# STM32f407layout_nonintegrated.net
KiCad netlist of a schematic drawn in EAGLE
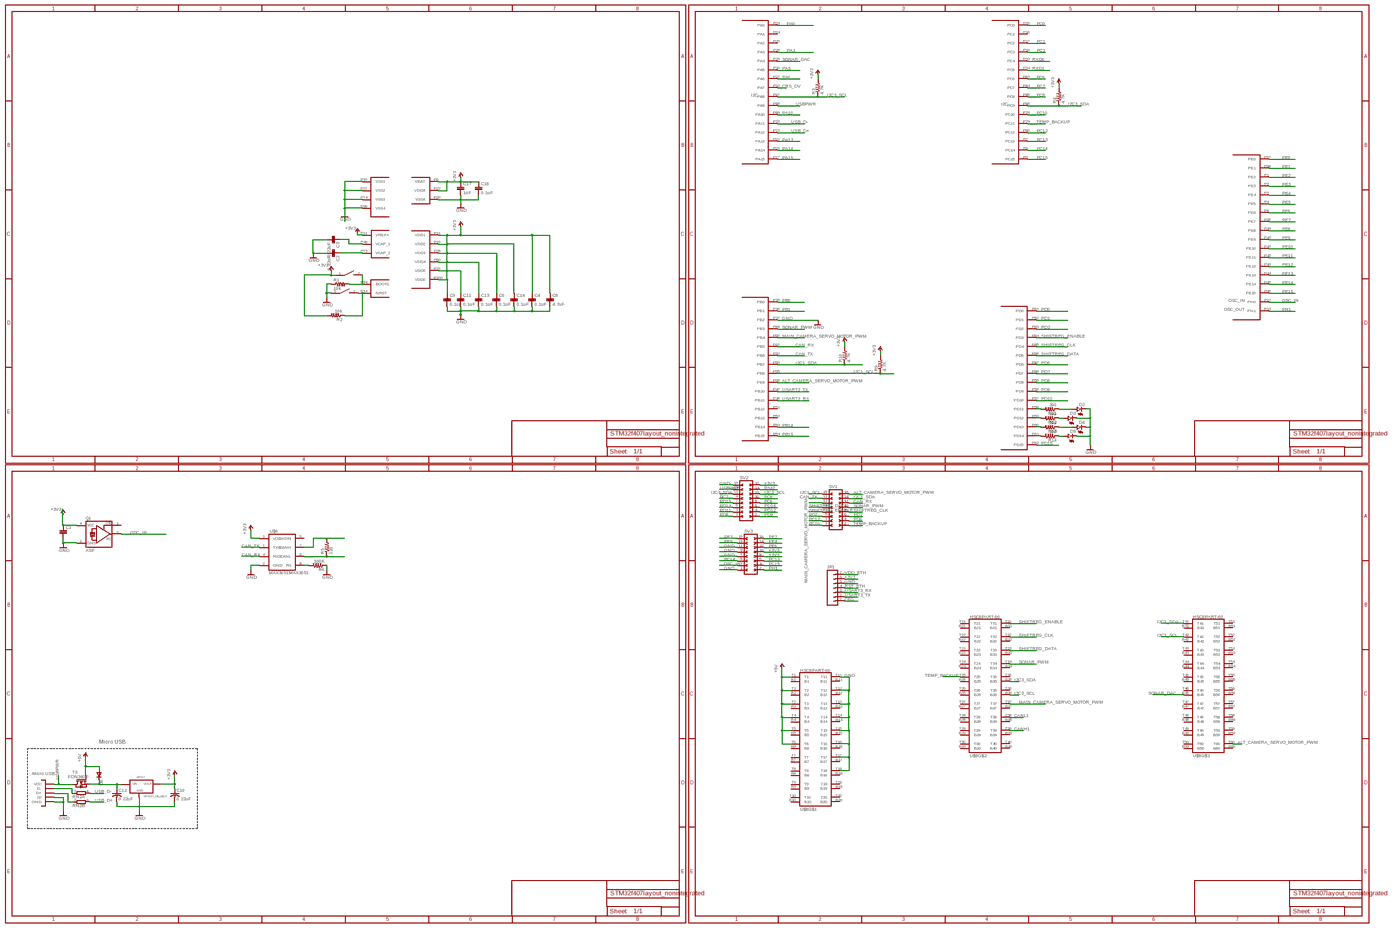
[diagram p0: schematic, sheet 1, overview]
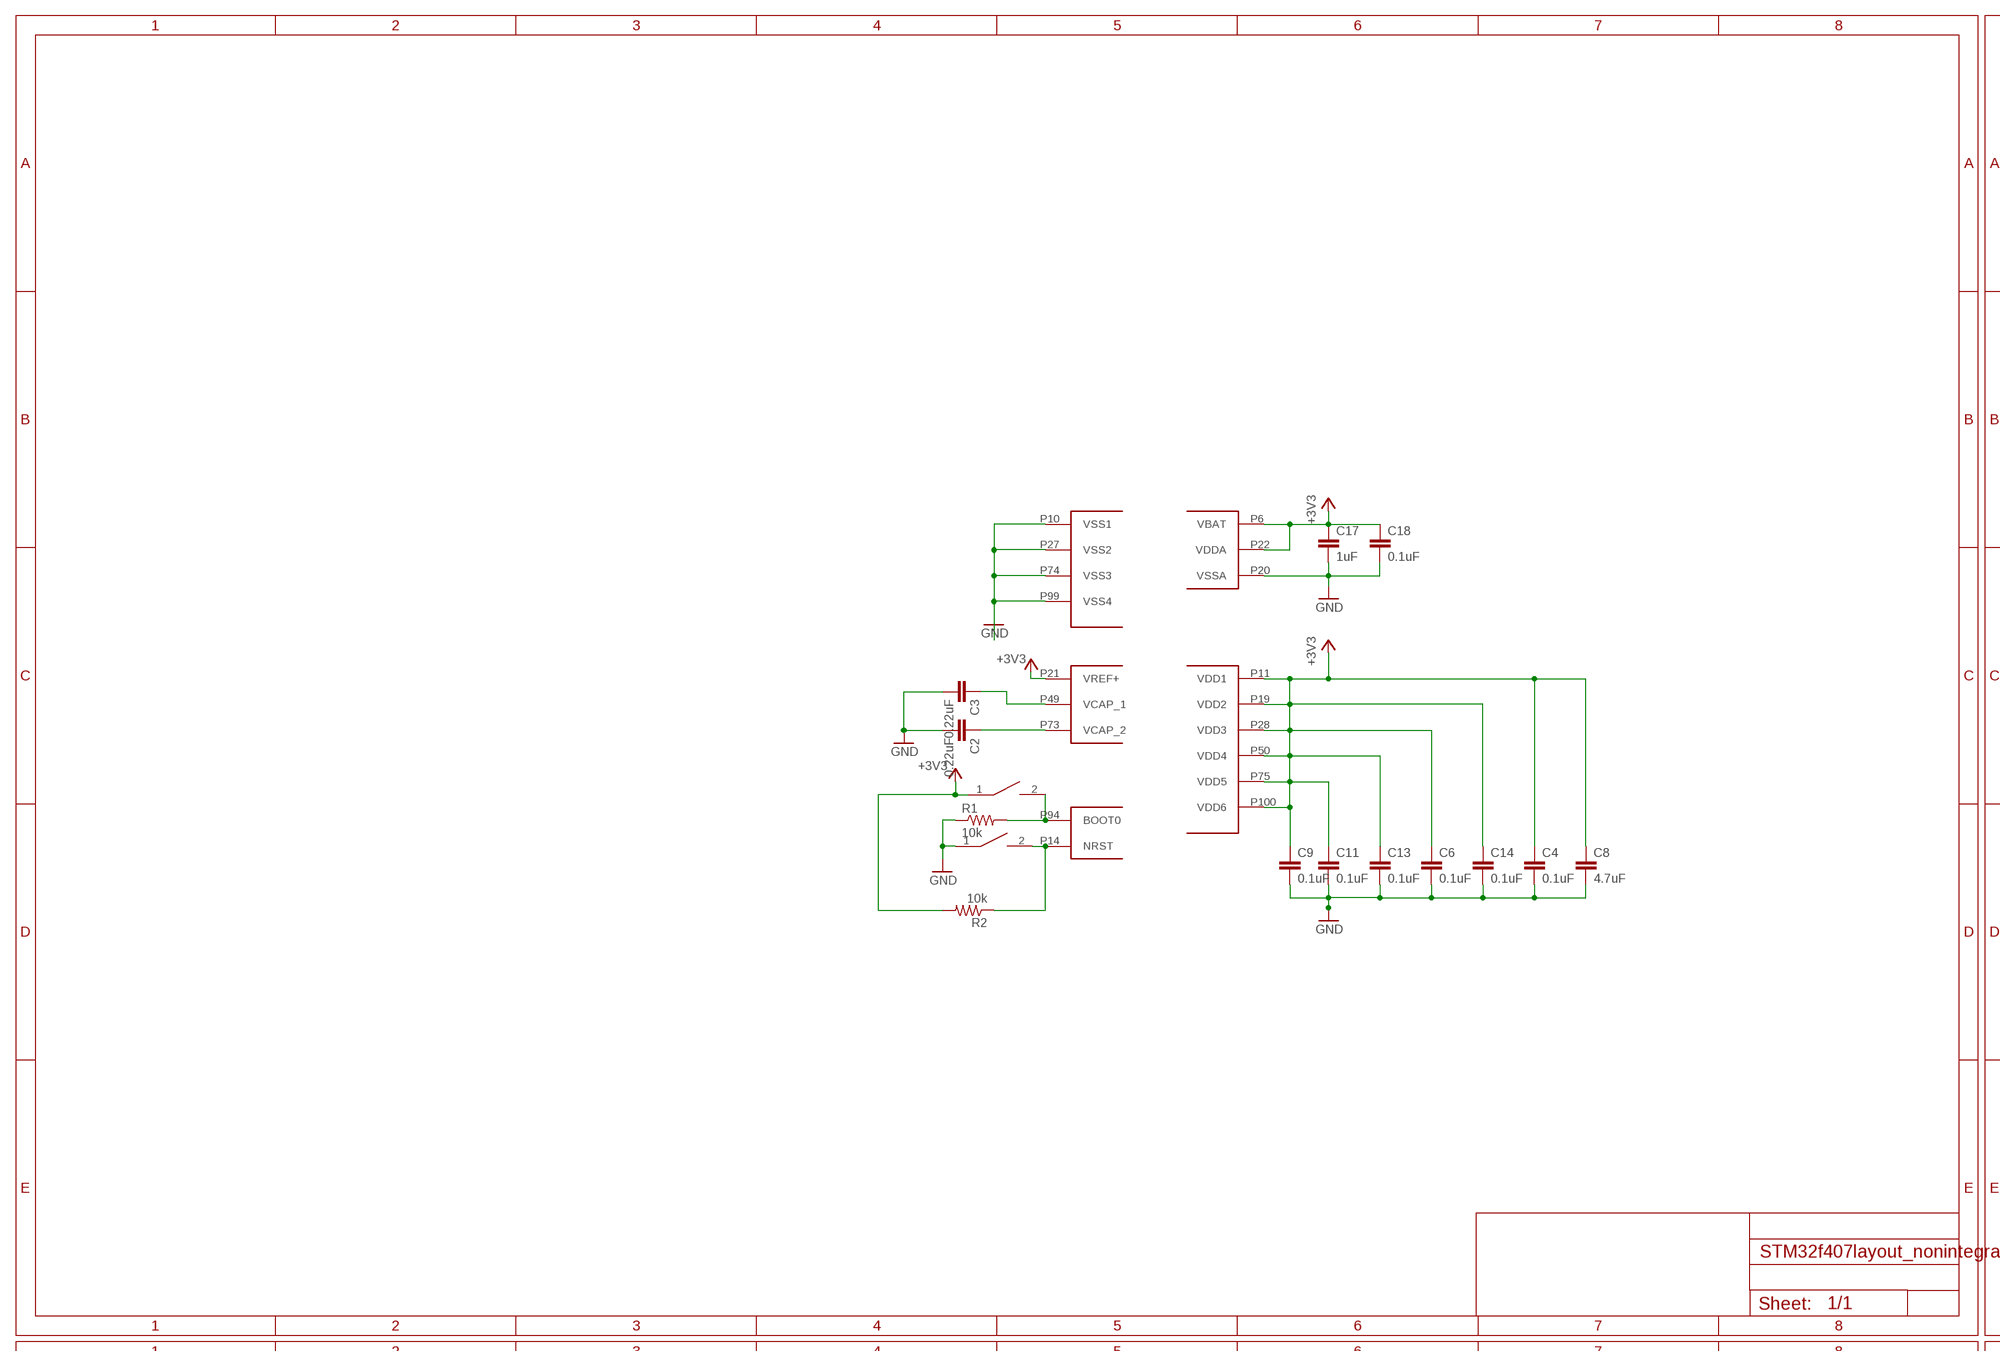
[diagram p1: schematic, sheet 1, part 1 of 4]
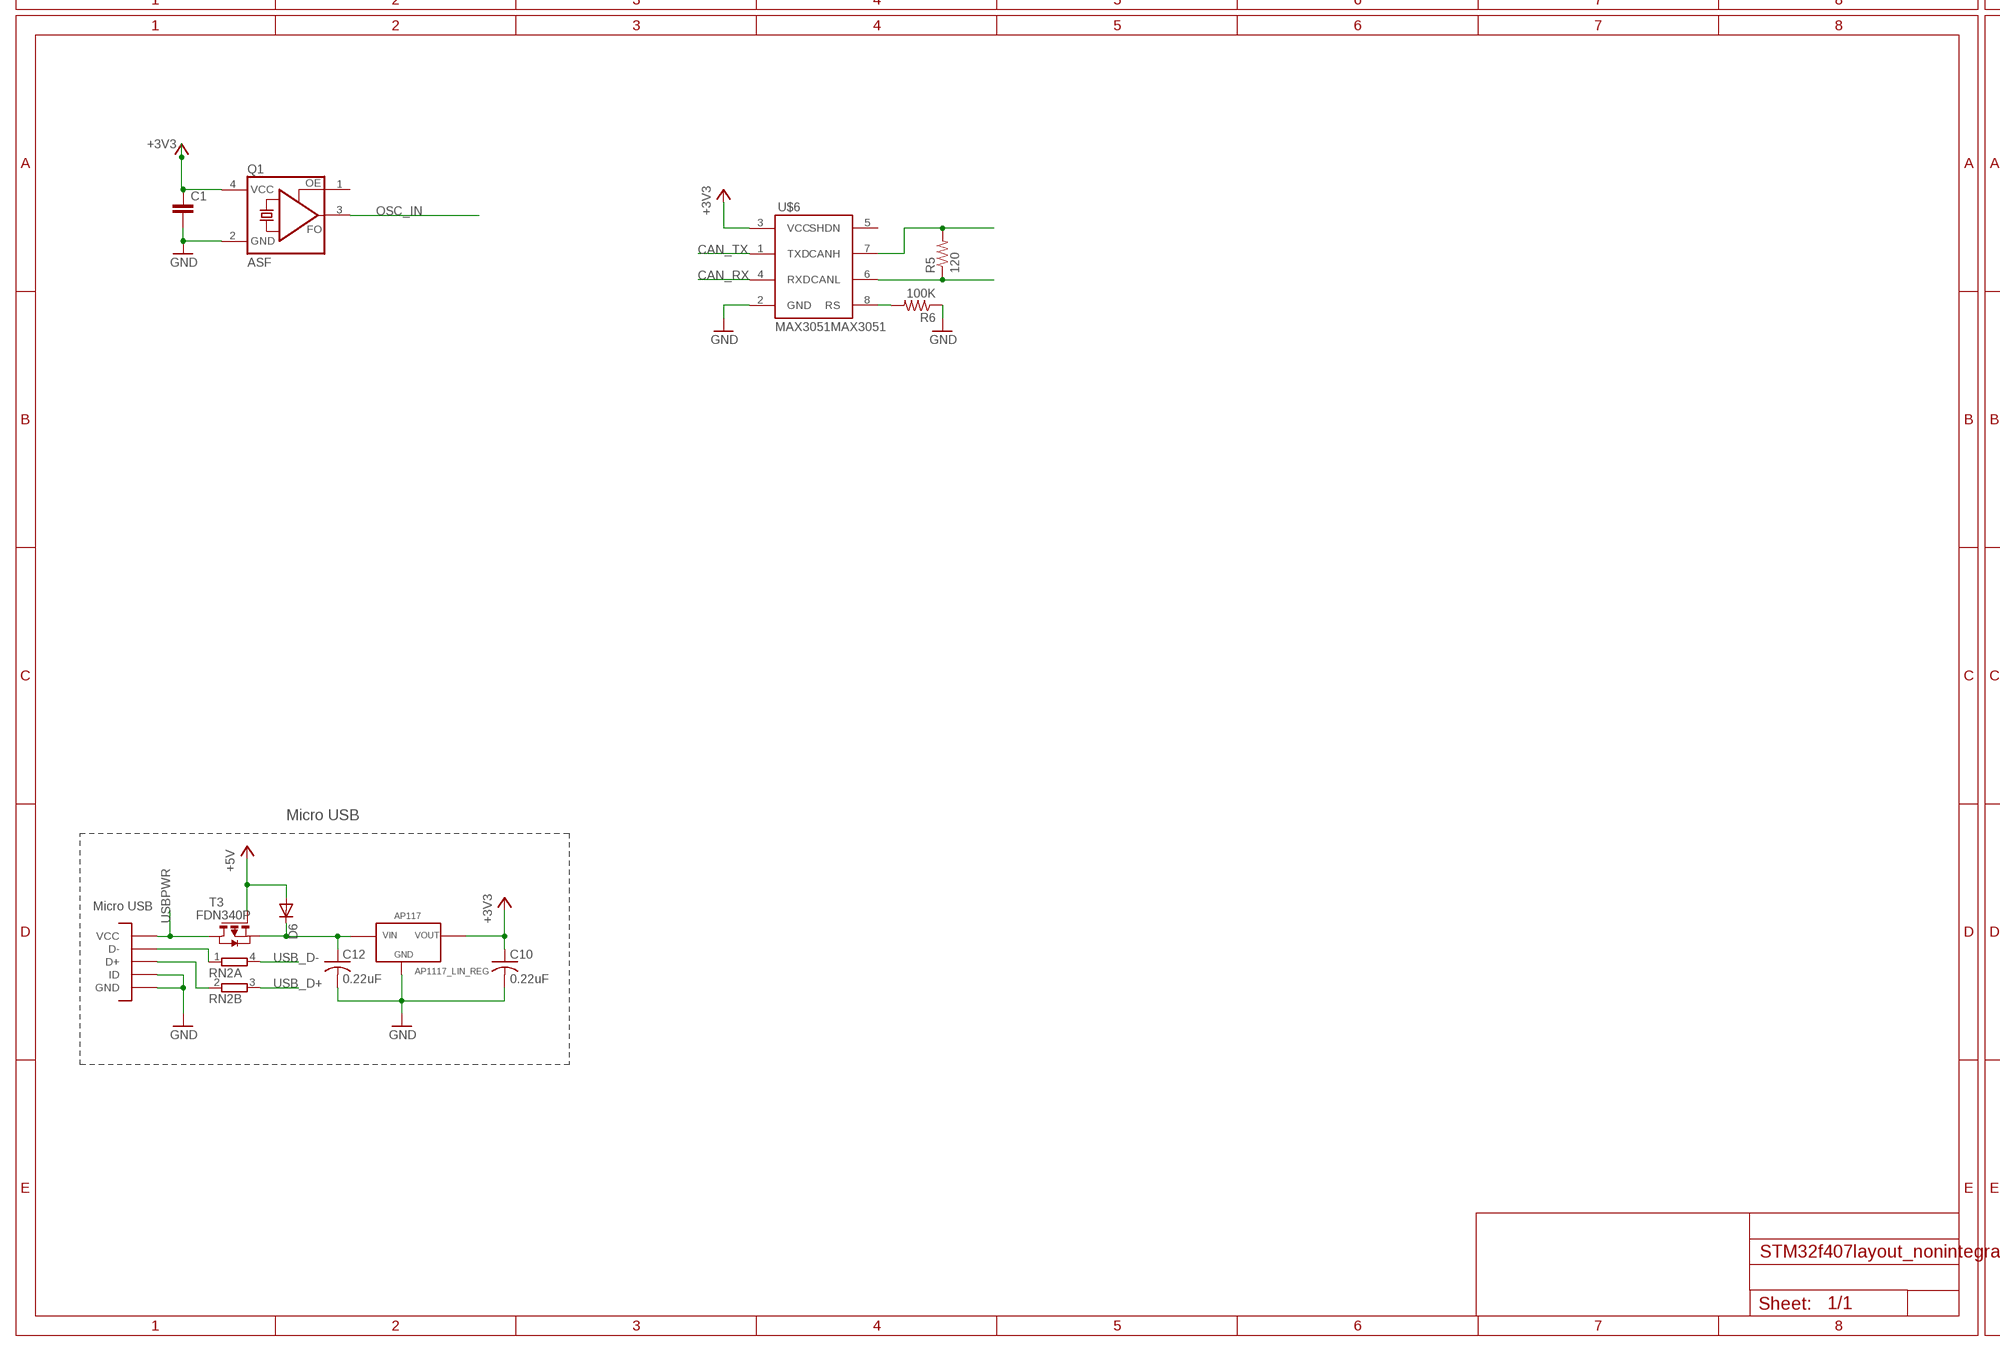
[diagram p2: schematic, sheet 1, part 2 of 4]
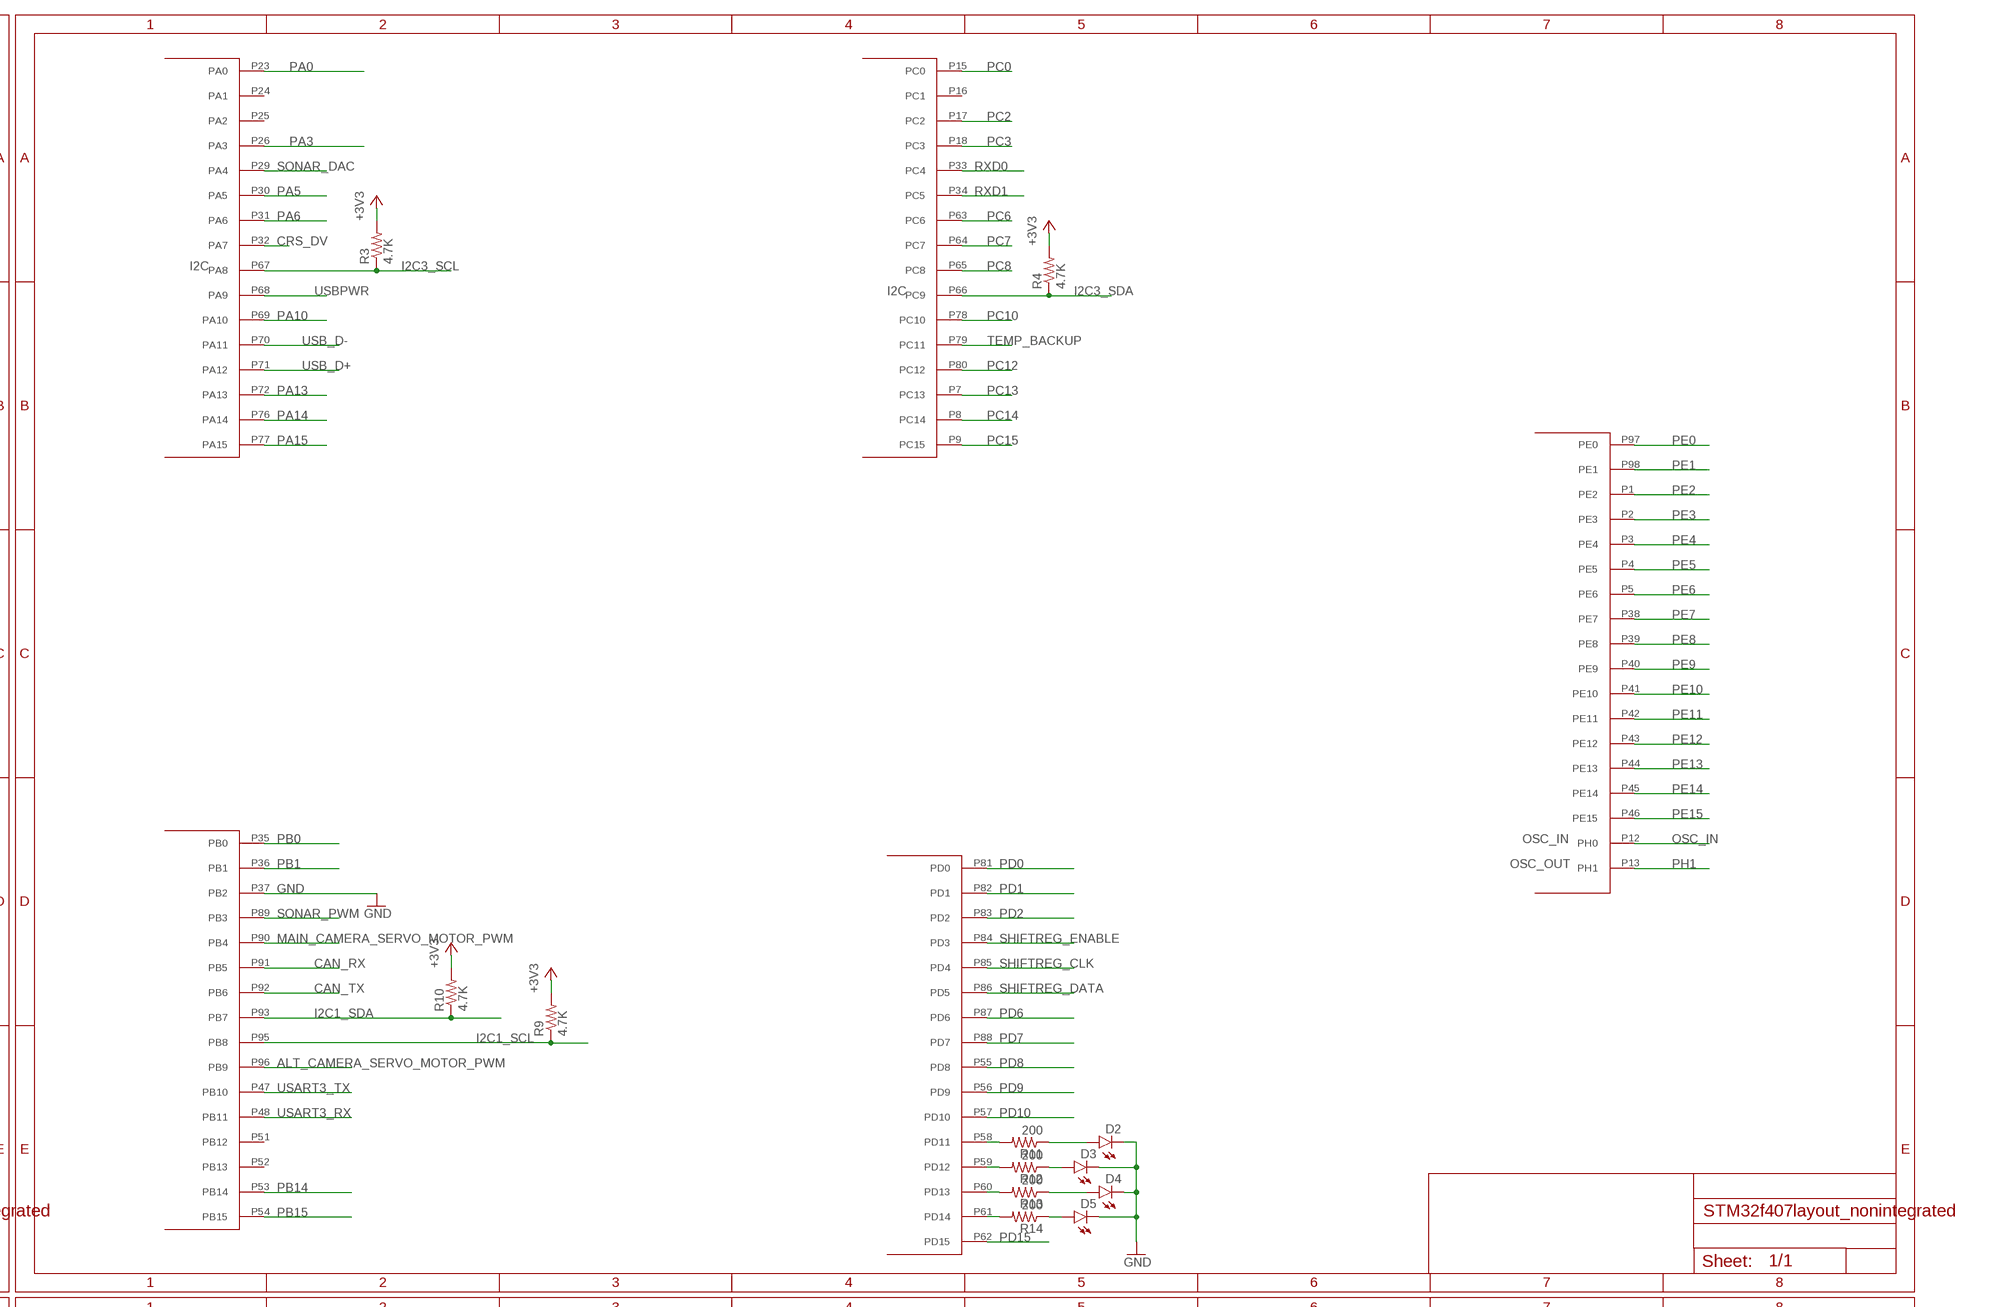
[diagram p3: schematic, sheet 1, part 3 of 4]
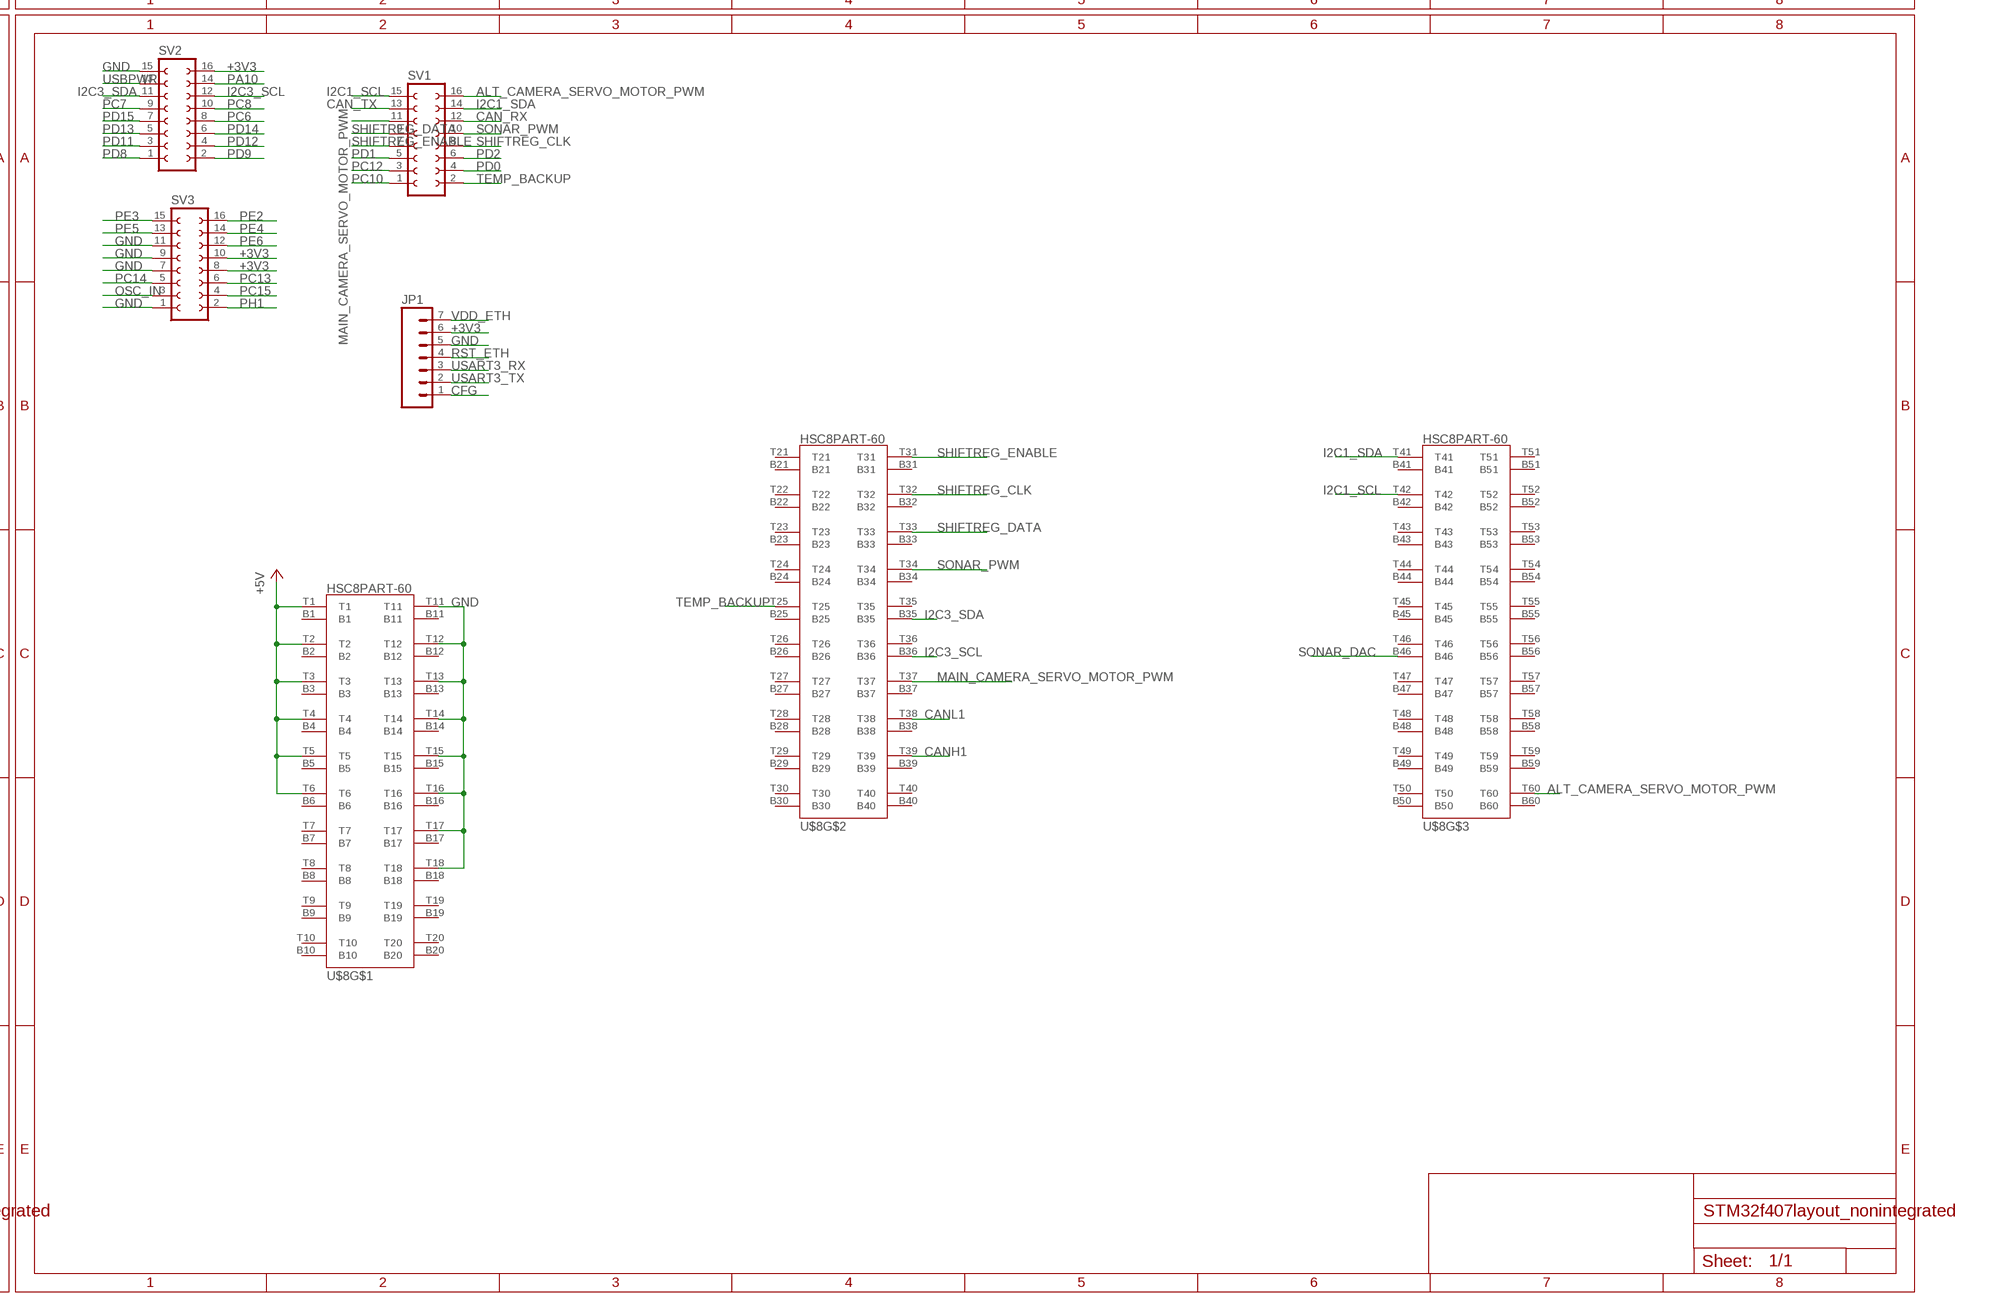
[diagram p4: schematic, sheet 1, part 4 of 4]

(export (version "E")
  (design (tool "Eeschema 10.0.6"))
  (components
    (comp (ref "C1")
      (value "CAP0603-CAP")
      (footprint "eagle-import:0603-CAP")
      (libsource (lib "eagle-import") (part "CAP0603-CAP"))
    )
    (comp (ref "C2")
      (value "0.22uF")
      (footprint "eagle-import:0603-CAP")
      (libsource (lib "eagle-import") (part "CAP0603-CAP"))
    )
    (comp (ref "C3")
      (value "0.22uF")
      (footprint "eagle-import:0603-CAP")
      (libsource (lib "eagle-import") (part "CAP0603-CAP"))
    )
    (comp (ref "C4")
      (value "0.1uF")
      (footprint "eagle-import:0603-CAP")
      (libsource (lib "eagle-import") (part "CAP0603-CAP"))
    )
    (comp (ref "C6")
      (value "0.1uF")
      (footprint "eagle-import:0603-CAP")
      (libsource (lib "eagle-import") (part "CAP0603-CAP"))
    )
    (comp (ref "C8")
      (value "4.7uF")
      (footprint "eagle-import:0603-CAP")
      (libsource (lib "eagle-import") (part "CAP0603-CAP"))
    )
    (comp (ref "C9")
      (value "0.1uF")
      (footprint "eagle-import:0603-CAP")
      (libsource (lib "eagle-import") (part "CAP0603-CAP"))
    )
    (comp (ref "C10")
      (value "0.22uF")
      (footprint "eagle-import:C0603")
      (libsource (lib "eagle-import") (part "C-USC0603"))
    )
    (comp (ref "C11")
      (value "0.1uF")
      (footprint "eagle-import:0603-CAP")
      (libsource (lib "eagle-import") (part "CAP0603-CAP"))
    )
    (comp (ref "C12")
      (value "0.22uF")
      (footprint "eagle-import:C0603")
      (libsource (lib "eagle-import") (part "C-USC0603"))
    )
    (comp (ref "C13")
      (value "0.1uF")
      (footprint "eagle-import:0603-CAP")
      (libsource (lib "eagle-import") (part "CAP0603-CAP"))
    )
    (comp (ref "C14")
      (value "0.1uF")
      (footprint "eagle-import:0603-CAP")
      (libsource (lib "eagle-import") (part "CAP0603-CAP"))
    )
    (comp (ref "C17")
      (value "1uF")
      (footprint "eagle-import:0603-CAP")
      (libsource (lib "eagle-import") (part "CAP0603-CAP"))
    )
    (comp (ref "C18")
      (value "0.1uF")
      (footprint "eagle-import:0603-CAP")
      (libsource (lib "eagle-import") (part "CAP0603-CAP"))
    )
    (comp (ref "D2")
      (value "LED0603")
      (footprint "eagle-import:LED-0603")
      (libsource (lib "eagle-import") (part "LED0603"))
    )
    (comp (ref "D3")
      (value "LED0603")
      (footprint "eagle-import:LED-0603")
      (libsource (lib "eagle-import") (part "LED0603"))
    )
    (comp (ref "D4")
      (value "LED0603")
      (footprint "eagle-import:LED-0603")
      (libsource (lib "eagle-import") (part "LED0603"))
    )
    (comp (ref "D5")
      (value "LED0603")
      (footprint "eagle-import:LED-0603")
      (libsource (lib "eagle-import") (part "LED0603"))
    )
    (comp (ref "D6")
      (value "DIODE-DO-214AC")
      (footprint "eagle-import:DO-214AC")
      (libsource (lib "eagle-import") (part "DIODE-DO-214AC"))
    )
    (comp (ref "JP1")
      (value "M07")
      (footprint "eagle-import:1X07")
      (libsource (lib "eagle-import") (part "M07"))
    )
    (comp (ref "Q1")
      (value "ASF")
      (footprint "eagle-import:ASF")
      (libsource (lib "eagle-import") (part "ASF"))
    )
    (comp (ref "R1")
      (value "10k")
      (footprint "eagle-import:0603-RES")
      (libsource (lib "eagle-import") (part "RESISTOR0603-RES"))
    )
    (comp (ref "R2")
      (value "10k")
      (footprint "eagle-import:0603-RES")
      (libsource (lib "eagle-import") (part "RESISTOR0603-RES"))
    )
    (comp (ref "R3")
      (value "4.7K")
      (footprint "eagle-import:0603-RES")
      (libsource (lib "eagle-import") (part "RESISTOR0603-RES"))
    )
    (comp (ref "R4")
      (value "4.7K")
      (footprint "eagle-import:0603-RES")
      (libsource (lib "eagle-import") (part "RESISTOR0603-RES"))
    )
    (comp (ref "R5")
      (value "120")
      (footprint "eagle-import:0603-RES")
      (libsource (lib "eagle-import") (part "RESISTOR0603-RES"))
    )
    (comp (ref "R6")
      (value "100K")
      (footprint "eagle-import:0603-RES")
      (libsource (lib "eagle-import") (part "RESISTOR0603-RES"))
    )
    (comp (ref "R9")
      (value "4.7K")
      (footprint "eagle-import:0603-RES")
      (libsource (lib "eagle-import") (part "RESISTOR0603-RES"))
    )
    (comp (ref "R10")
      (value "4.7K")
      (footprint "eagle-import:0603-RES")
      (libsource (lib "eagle-import") (part "RESISTOR0603-RES"))
    )
    (comp (ref "R11")
      (value "200")
      (footprint "eagle-import:0603-RES")
      (libsource (lib "eagle-import") (part "RESISTOR0603-RES"))
    )
    (comp (ref "R12")
      (value "200")
      (footprint "eagle-import:0603-RES")
      (libsource (lib "eagle-import") (part "RESISTOR0603-RES"))
    )
    (comp (ref "R13")
      (value "200")
      (footprint "eagle-import:0603-RES")
      (libsource (lib "eagle-import") (part "RESISTOR0603-RES"))
    )
    (comp (ref "R14")
      (value "200")
      (footprint "eagle-import:0603-RES")
      (libsource (lib "eagle-import") (part "RESISTOR0603-RES"))
    )
    (comp (ref "RN2")
      (value "2R-NEXBV4V")
      (footprint "eagle-import:EXBV4V")
      (fields (field (name "MF") "Rohm Semiconductor") (field (name "MPN") "MNR12ERAPJ220"))
      (libsource (lib "eagle-import") (part "2R-NEXBV4V"))
    )
    (comp (ref "SV1")
      (value "FE08-2")
      (footprint "eagle-import:FE08-2")
      (libsource (lib "eagle-import") (part "FE08-2"))
    )
    (comp (ref "SV2")
      (value "FE08-2")
      (footprint "eagle-import:FE08-2")
      (libsource (lib "eagle-import") (part "FE08-2"))
    )
    (comp (ref "SV3")
      (value "FE08-2")
      (footprint "eagle-import:FE08-2")
      (libsource (lib "eagle-import") (part "FE08-2"))
    )
    (comp (ref "T3")
      (value "FDN340P")
      (footprint "eagle-import:SOT-23")
      (libsource (lib "eagle-import") (part "FDN340P"))
    )
    (comp (ref "T4")
      (value "AP1117_LIN_REG")
      (footprint "eagle-import:SOT223")
      (libsource (lib "eagle-import") (part "AP1117_LIN_REG"))
    )
    (comp (ref "U$1")
      (value "STM32F4")
      (footprint "eagle-import:LQFP100")
      (libsource (lib "eagle-import") (part "STM32F4"))
    )
    (comp (ref "U$2")
      (value "SWITCH")
      (footprint "eagle-import:SW_2512")
      (libsource (lib "eagle-import") (part "SWITCH"))
    )
    (comp (ref "U$3")
      (value "SWITCH")
      (footprint "eagle-import:SW_2512")
      (libsource (lib "eagle-import") (part "SWITCH"))
    )
    (comp (ref "U$5")
      (value "MICROUSB")
      (footprint "eagle-import:MICRO_B")
      (libsource (lib "eagle-import") (part "MICROUSB"))
    )
    (comp (ref "U$6")
      (value "MAX3051MAX3051")
      (footprint "eagle-import:SOT23-8L")
      (libsource (lib "eagle-import") (part "MAX3051MAX3051"))
    )
    (comp (ref "U$8")
      (value "HSC8PART-60")
      (footprint "eagle-import:HSC8-60PINOUUT")
      (libsource (lib "eagle-import") (part "HSC8PART-60"))
    )
  )
  (nets
    (net (code "1") (name "+3V3") (class "Default")
      (node (ref "C1") (pin "1") (pinfunction "1_1") (pintype "passive"))
      (node (ref "C10") (pin "1") (pinfunction "1_1") (pintype "passive"))
      (node (ref "C11") (pin "1") (pinfunction "1_1") (pintype "passive"))
      (node (ref "C13") (pin "1") (pinfunction "1_1") (pintype "passive"))
      (node (ref "C14") (pin "1") (pinfunction "1_1") (pintype "passive"))
      (node (ref "C17") (pin "1") (pinfunction "1_1") (pintype "passive"))
      (node (ref "C18") (pin "1") (pinfunction "1_1") (pintype "passive"))
      (node (ref "C4") (pin "1") (pinfunction "1_1") (pintype "passive"))
      (node (ref "C6") (pin "1") (pinfunction "1_1") (pintype "passive"))
      (node (ref "C8") (pin "1") (pinfunction "1_1") (pintype "passive"))
      (node (ref "C9") (pin "1") (pinfunction "1_1") (pintype "passive"))
      (node (ref "JP1") (pin "6") (pinfunction "6_6") (pintype "passive"))
      (node (ref "Q1") (pin "4") (pinfunction "VCC_4") (pintype "power_in"))
      (node (ref "R10") (pin "2") (pinfunction "2_2") (pintype "passive"))
      (node (ref "R2") (pin "2") (pinfunction "2_2") (pintype "passive"))
      (node (ref "R3") (pin "2") (pinfunction "2_2") (pintype "passive"))
      (node (ref "R4") (pin "2") (pinfunction "2_2") (pintype "passive"))
      (node (ref "R9") (pin "2") (pinfunction "2_2") (pintype "passive"))
      (node (ref "SV2") (pin "16") (pinfunction "16_16") (pintype "passive"))
      (node (ref "SV3") (pin "10") (pinfunction "10_10") (pintype "passive"))
      (node (ref "SV3") (pin "8") (pinfunction "8_8") (pintype "passive"))
      (node (ref "T4") (pin "TAB") (pinfunction "VOUT_TAB") (pintype "output"))
      (node (ref "T4") (pin "VOUT") (pinfunction "VOUT_VOUT") (pintype "output"))
      (node (ref "U$1") (pin "P100") (pinfunction "VDD6_P100") (pintype "bidirectional"))
      (node (ref "U$1") (pin "P11") (pinfunction "VDD1_P11") (pintype "bidirectional"))
      (node (ref "U$1") (pin "P19") (pinfunction "VDD2_P19") (pintype "bidirectional"))
      (node (ref "U$1") (pin "P21") (pinfunction "VREF+_P21") (pintype "bidirectional"))
      (node (ref "U$1") (pin "P22") (pinfunction "VDDA_P22") (pintype "bidirectional"))
      (node (ref "U$1") (pin "P28") (pinfunction "VDD3_P28") (pintype "bidirectional"))
      (node (ref "U$1") (pin "P50") (pinfunction "VDD4_P50") (pintype "bidirectional"))
      (node (ref "U$1") (pin "P6") (pinfunction "VBAT_P6") (pintype "bidirectional"))
      (node (ref "U$1") (pin "P75") (pinfunction "VDD5_P75") (pintype "bidirectional"))
      (node (ref "U$3") (pin "1") (pinfunction "P$1_1") (pintype "bidirectional"))
      (node (ref "U$6") (pin "3") (pinfunction "VCC_3") (pintype "bidirectional"))
    )
    (net (code "2") (name "+5V") (class "Default")
      (node (ref "D6") (pin "A") (pinfunction "A_A") (pintype "passive"))
      (node (ref "T3") (pin "3") (pinfunction "G_3") (pintype "passive"))
      (node (ref "U$8") (pin "T1") (pinfunction "T1_T1") (pintype "bidirectional"))
      (node (ref "U$8") (pin "T2") (pinfunction "T2_T2") (pintype "bidirectional"))
      (node (ref "U$8") (pin "T3") (pinfunction "T3_T3") (pintype "bidirectional"))
      (node (ref "U$8") (pin "T4") (pinfunction "T4_T4") (pintype "bidirectional"))
      (node (ref "U$8") (pin "T5") (pinfunction "T5_T5") (pintype "bidirectional"))
      (node (ref "U$8") (pin "T6") (pinfunction "T6_T6") (pintype "bidirectional"))
    )
    (net (code "3") (name "/ALT_CAMERA_SERVO_MOTOR_PWM") (class "Default")
      (node (ref "SV1") (pin "16") (pinfunction "16_16") (pintype "passive"))
      (node (ref "U$1") (pin "P96") (pinfunction "PB9_P96") (pintype "bidirectional"))
      (node (ref "U$8") (pin "T60") (pinfunction "T60_T60") (pintype "bidirectional"))
    )
    (net (code "4") (name "/CANH1") (class "Default")
      (node (ref "R5") (pin "2") (pinfunction "2_2") (pintype "passive"))
      (node (ref "U$6") (pin "7") (pinfunction "CANH_7") (pintype "bidirectional"))
      (node (ref "U$8") (pin "T39") (pinfunction "T39_T39") (pintype "bidirectional"))
    )
    (net (code "5") (name "/CANL1") (class "Default")
      (node (ref "R5") (pin "1") (pinfunction "1_1") (pintype "passive"))
      (node (ref "U$6") (pin "6") (pinfunction "CANL_6") (pintype "bidirectional"))
      (node (ref "U$8") (pin "T38") (pinfunction "T38_T38") (pintype "bidirectional"))
    )
    (net (code "6") (name "/CAN_RX") (class "Default")
      (node (ref "SV1") (pin "12") (pinfunction "12_12") (pintype "passive"))
      (node (ref "U$1") (pin "P91") (pinfunction "PB5_P91") (pintype "bidirectional"))
      (node (ref "U$6") (pin "4") (pinfunction "RXD_4") (pintype "bidirectional"))
    )
    (net (code "7") (name "/CAN_TX") (class "Default")
      (node (ref "SV1") (pin "13") (pinfunction "13_13") (pintype "passive"))
      (node (ref "U$1") (pin "P92") (pinfunction "PB6_P92") (pintype "bidirectional"))
      (node (ref "U$6") (pin "1") (pinfunction "TXD_1") (pintype "bidirectional"))
    )
    (net (code "8") (name "/CFG") (class "Default")
      (node (ref "JP1") (pin "1") (pinfunction "1_1") (pintype "passive"))
    )
    (net (code "9") (name "/CRS_DV") (class "Default")
      (node (ref "U$1") (pin "P32") (pinfunction "PA7_P32") (pintype "bidirectional"))
    )
    (net (code "10") (name "/I2C1_SCL") (class "Default")
      (node (ref "R9") (pin "1") (pinfunction "1_1") (pintype "passive"))
      (node (ref "SV1") (pin "15") (pinfunction "15_15") (pintype "passive"))
      (node (ref "U$1") (pin "P95") (pinfunction "PB8_P95") (pintype "bidirectional"))
      (node (ref "U$8") (pin "T42") (pinfunction "T42_T42") (pintype "bidirectional"))
    )
    (net (code "11") (name "/I2C1_SDA") (class "Default")
      (node (ref "R10") (pin "1") (pinfunction "1_1") (pintype "passive"))
      (node (ref "SV1") (pin "14") (pinfunction "14_14") (pintype "passive"))
      (node (ref "U$1") (pin "P93") (pinfunction "PB7_P93") (pintype "bidirectional"))
      (node (ref "U$8") (pin "T41") (pinfunction "T41_T41") (pintype "bidirectional"))
    )
    (net (code "12") (name "/I2C3_SCL") (class "Default")
      (node (ref "R3") (pin "1") (pinfunction "1_1") (pintype "passive"))
      (node (ref "SV2") (pin "12") (pinfunction "12_12") (pintype "passive"))
      (node (ref "U$1") (pin "P67") (pinfunction "PA8_P67") (pintype "bidirectional"))
      (node (ref "U$8") (pin "B36") (pinfunction "B36_B36") (pintype "bidirectional"))
    )
    (net (code "13") (name "/I2C3_SDA") (class "Default")
      (node (ref "R4") (pin "1") (pinfunction "1_1") (pintype "passive"))
      (node (ref "SV2") (pin "11") (pinfunction "11_11") (pintype "passive"))
      (node (ref "U$1") (pin "P66") (pinfunction "PC9_P66") (pintype "bidirectional"))
      (node (ref "U$8") (pin "B35") (pinfunction "B35_B35") (pintype "bidirectional"))
    )
    (net (code "14") (name "/MAIN_CAMERA_SERVO_MOTOR_PWM") (class "Default")
      (node (ref "SV1") (pin "11") (pinfunction "11_11") (pintype "passive"))
      (node (ref "U$1") (pin "P90") (pinfunction "PB4_P90") (pintype "bidirectional"))
      (node (ref "U$8") (pin "T37") (pinfunction "T37_T37") (pintype "bidirectional"))
    )
    (net (code "15") (name "/OSC_IN") (class "Default")
      (node (ref "Q1") (pin "3") (pinfunction "FO_3") (pintype "output"))
      (node (ref "SV3") (pin "3") (pinfunction "3_3") (pintype "passive"))
      (node (ref "U$1") (pin "P12") (pinfunction "PH0_P12") (pintype "bidirectional"))
    )
    (net (code "16") (name "/PA0") (class "Default")
      (node (ref "U$1") (pin "P23") (pinfunction "PA0_P23") (pintype "bidirectional"))
    )
    (net (code "17") (name "/PA3") (class "Default")
      (node (ref "U$1") (pin "P26") (pinfunction "PA3_P26") (pintype "bidirectional"))
    )
    (net (code "18") (name "/PA5") (class "Default")
      (node (ref "U$1") (pin "P30") (pinfunction "PA5_P30") (pintype "bidirectional"))
    )
    (net (code "19") (name "/PA6") (class "Default")
      (node (ref "U$1") (pin "P31") (pinfunction "PA6_P31") (pintype "bidirectional"))
    )
    (net (code "20") (name "/PA10") (class "Default")
      (node (ref "SV2") (pin "14") (pinfunction "14_14") (pintype "passive"))
      (node (ref "U$1") (pin "P69") (pinfunction "PA10_P69") (pintype "bidirectional"))
    )
    (net (code "21") (name "/PA13") (class "Default")
      (node (ref "U$1") (pin "P72") (pinfunction "PA13_P72") (pintype "bidirectional"))
    )
    (net (code "22") (name "/PA14") (class "Default")
      (node (ref "U$1") (pin "P76") (pinfunction "PA14_P76") (pintype "bidirectional"))
    )
    (net (code "23") (name "/PA15") (class "Default")
      (node (ref "U$1") (pin "P77") (pinfunction "PA15_P77") (pintype "bidirectional"))
    )
    (net (code "24") (name "/PB0") (class "Default")
      (node (ref "U$1") (pin "P35") (pinfunction "PB0_P35") (pintype "bidirectional"))
    )
    (net (code "25") (name "/PB1") (class "Default")
      (node (ref "U$1") (pin "P36") (pinfunction "PB1_P36") (pintype "bidirectional"))
    )
    (net (code "26") (name "/PB14") (class "Default")
      (node (ref "U$1") (pin "P53") (pinfunction "PB14_P53") (pintype "bidirectional"))
    )
    (net (code "27") (name "/PB15") (class "Default")
      (node (ref "U$1") (pin "P54") (pinfunction "PB15_P54") (pintype "bidirectional"))
    )
    (net (code "28") (name "/PC0") (class "Default")
      (node (ref "U$1") (pin "P15") (pinfunction "PC0_P15") (pintype "bidirectional"))
    )
    (net (code "29") (name "/PC2") (class "Default")
      (node (ref "U$1") (pin "P17") (pinfunction "PC2_P17") (pintype "bidirectional"))
    )
    (net (code "30") (name "/PC3") (class "Default")
      (node (ref "U$1") (pin "P18") (pinfunction "PC3_P18") (pintype "bidirectional"))
    )
    (net (code "31") (name "/PC6") (class "Default")
      (node (ref "SV2") (pin "8") (pinfunction "8_8") (pintype "passive"))
      (node (ref "U$1") (pin "P63") (pinfunction "PC6_P63") (pintype "bidirectional"))
    )
    (net (code "32") (name "/PC7") (class "Default")
      (node (ref "SV2") (pin "9") (pinfunction "9_9") (pintype "passive"))
      (node (ref "U$1") (pin "P64") (pinfunction "PC7_P64") (pintype "bidirectional"))
    )
    (net (code "33") (name "/PC8") (class "Default")
      (node (ref "SV2") (pin "10") (pinfunction "10_10") (pintype "passive"))
      (node (ref "U$1") (pin "P65") (pinfunction "PC8_P65") (pintype "bidirectional"))
    )
    (net (code "34") (name "/PC10") (class "Default")
      (node (ref "SV1") (pin "1") (pinfunction "1_1") (pintype "passive"))
      (node (ref "U$1") (pin "P78") (pinfunction "PC10_P78") (pintype "bidirectional"))
    )
    (net (code "35") (name "/PC12") (class "Default")
      (node (ref "SV1") (pin "3") (pinfunction "3_3") (pintype "passive"))
      (node (ref "U$1") (pin "P80") (pinfunction "PC12_P80") (pintype "bidirectional"))
    )
    (net (code "36") (name "/PC13") (class "Default")
      (node (ref "SV3") (pin "6") (pinfunction "6_6") (pintype "passive"))
      (node (ref "U$1") (pin "P7") (pinfunction "PC13_P7") (pintype "bidirectional"))
    )
    (net (code "37") (name "/PC14") (class "Default")
      (node (ref "SV3") (pin "5") (pinfunction "5_5") (pintype "passive"))
      (node (ref "U$1") (pin "P8") (pinfunction "PC14_P8") (pintype "bidirectional"))
    )
    (net (code "38") (name "/PC15") (class "Default")
      (node (ref "SV3") (pin "4") (pinfunction "4_4") (pintype "passive"))
      (node (ref "U$1") (pin "P9") (pinfunction "PC15_P9") (pintype "bidirectional"))
    )
    (net (code "39") (name "/PD0") (class "Default")
      (node (ref "SV1") (pin "4") (pinfunction "4_4") (pintype "passive"))
      (node (ref "U$1") (pin "P81") (pinfunction "PD0_P81") (pintype "bidirectional"))
    )
    (net (code "40") (name "/PD1") (class "Default")
      (node (ref "SV1") (pin "5") (pinfunction "5_5") (pintype "passive"))
      (node (ref "U$1") (pin "P82") (pinfunction "PD1_P82") (pintype "bidirectional"))
    )
    (net (code "41") (name "/PD2") (class "Default")
      (node (ref "SV1") (pin "6") (pinfunction "6_6") (pintype "passive"))
      (node (ref "U$1") (pin "P83") (pinfunction "PD2_P83") (pintype "bidirectional"))
    )
    (net (code "42") (name "/PD6") (class "Default")
      (node (ref "U$1") (pin "P87") (pinfunction "PD6_P87") (pintype "bidirectional"))
    )
    (net (code "43") (name "/PD7") (class "Default")
      (node (ref "U$1") (pin "P88") (pinfunction "PD7_P88") (pintype "bidirectional"))
    )
    (net (code "44") (name "/PD8") (class "Default")
      (node (ref "SV2") (pin "1") (pinfunction "1_1") (pintype "passive"))
      (node (ref "U$1") (pin "P55") (pinfunction "PD8_P55") (pintype "bidirectional"))
    )
    (net (code "45") (name "/PD9") (class "Default")
      (node (ref "SV2") (pin "2") (pinfunction "2_2") (pintype "passive"))
      (node (ref "U$1") (pin "P56") (pinfunction "PD9_P56") (pintype "bidirectional"))
    )
    (net (code "46") (name "/PD10") (class "Default")
      (node (ref "U$1") (pin "P57") (pinfunction "PD10_P57") (pintype "bidirectional"))
    )
    (net (code "47") (name "/PD11") (class "Default")
      (node (ref "R11") (pin "2") (pinfunction "2_2") (pintype "passive"))
      (node (ref "SV2") (pin "3") (pinfunction "3_3") (pintype "passive"))
      (node (ref "U$1") (pin "P58") (pinfunction "PD11_P58") (pintype "bidirectional"))
    )
    (net (code "48") (name "/PD12") (class "Default")
      (node (ref "R12") (pin "2") (pinfunction "2_2") (pintype "passive"))
      (node (ref "SV2") (pin "4") (pinfunction "4_4") (pintype "passive"))
      (node (ref "U$1") (pin "P59") (pinfunction "PD12_P59") (pintype "bidirectional"))
    )
    (net (code "49") (name "/PD13") (class "Default")
      (node (ref "R13") (pin "2") (pinfunction "2_2") (pintype "passive"))
      (node (ref "SV2") (pin "5") (pinfunction "5_5") (pintype "passive"))
      (node (ref "U$1") (pin "P60") (pinfunction "PD13_P60") (pintype "bidirectional"))
    )
    (net (code "50") (name "/PD14") (class "Default")
      (node (ref "R14") (pin "2") (pinfunction "2_2") (pintype "passive"))
      (node (ref "SV2") (pin "6") (pinfunction "6_6") (pintype "passive"))
      (node (ref "U$1") (pin "P61") (pinfunction "PD14_P61") (pintype "bidirectional"))
    )
    (net (code "51") (name "/PD15") (class "Default")
      (node (ref "SV2") (pin "7") (pinfunction "7_7") (pintype "passive"))
      (node (ref "U$1") (pin "P62") (pinfunction "PD15_P62") (pintype "bidirectional"))
    )
    (net (code "52") (name "/PE0") (class "Default")
      (node (ref "U$1") (pin "P97") (pinfunction "PE0_P97") (pintype "bidirectional"))
    )
    (net (code "53") (name "/PE1") (class "Default")
      (node (ref "U$1") (pin "P98") (pinfunction "PE1_P98") (pintype "bidirectional"))
    )
    (net (code "54") (name "/PE2") (class "Default")
      (node (ref "SV3") (pin "16") (pinfunction "16_16") (pintype "passive"))
      (node (ref "U$1") (pin "P1") (pinfunction "PE2_P1") (pintype "bidirectional"))
    )
    (net (code "55") (name "/PE3") (class "Default")
      (node (ref "SV3") (pin "15") (pinfunction "15_15") (pintype "passive"))
      (node (ref "U$1") (pin "P2") (pinfunction "PE3_P2") (pintype "bidirectional"))
    )
    (net (code "56") (name "/PE4") (class "Default")
      (node (ref "SV3") (pin "14") (pinfunction "14_14") (pintype "passive"))
      (node (ref "U$1") (pin "P3") (pinfunction "PE4_P3") (pintype "bidirectional"))
    )
    (net (code "57") (name "/PE5") (class "Default")
      (node (ref "SV3") (pin "13") (pinfunction "13_13") (pintype "passive"))
      (node (ref "U$1") (pin "P4") (pinfunction "PE5_P4") (pintype "bidirectional"))
    )
    (net (code "58") (name "/PE6") (class "Default")
      (node (ref "SV3") (pin "12") (pinfunction "12_12") (pintype "passive"))
      (node (ref "U$1") (pin "P5") (pinfunction "PE6_P5") (pintype "bidirectional"))
    )
    (net (code "59") (name "/PE7") (class "Default")
      (node (ref "U$1") (pin "P38") (pinfunction "PE7_P38") (pintype "bidirectional"))
    )
    (net (code "60") (name "/PE8") (class "Default")
      (node (ref "U$1") (pin "P39") (pinfunction "PE8_P39") (pintype "bidirectional"))
    )
    (net (code "61") (name "/PE9") (class "Default")
      (node (ref "U$1") (pin "P40") (pinfunction "PE9_P40") (pintype "bidirectional"))
    )
    (net (code "62") (name "/PE10") (class "Default")
      (node (ref "U$1") (pin "P41") (pinfunction "PE10_P41") (pintype "bidirectional"))
    )
    (net (code "63") (name "/PE11") (class "Default")
      (node (ref "U$1") (pin "P42") (pinfunction "PE11_P42") (pintype "bidirectional"))
    )
    (net (code "64") (name "/PE12") (class "Default")
      (node (ref "U$1") (pin "P43") (pinfunction "PE12_P43") (pintype "bidirectional"))
    )
    (net (code "65") (name "/PE13") (class "Default")
      (node (ref "U$1") (pin "P44") (pinfunction "PE13_P44") (pintype "bidirectional"))
    )
    (net (code "66") (name "/PE14") (class "Default")
      (node (ref "U$1") (pin "P45") (pinfunction "PE14_P45") (pintype "bidirectional"))
    )
    (net (code "67") (name "/PE15") (class "Default")
      (node (ref "U$1") (pin "P46") (pinfunction "PE15_P46") (pintype "bidirectional"))
    )
    (net (code "68") (name "/PH1") (class "Default")
      (node (ref "SV3") (pin "2") (pinfunction "2_2") (pintype "passive"))
      (node (ref "U$1") (pin "P13") (pinfunction "PH1_P13") (pintype "bidirectional"))
    )
    (net (code "69") (name "/RST_ETH") (class "Default")
      (node (ref "JP1") (pin "4") (pinfunction "4_4") (pintype "passive"))
    )
    (net (code "70") (name "/RXD0") (class "Default")
      (node (ref "U$1") (pin "P33") (pinfunction "PC4_P33") (pintype "bidirectional"))
    )
    (net (code "71") (name "/RXD1") (class "Default")
      (node (ref "U$1") (pin "P34") (pinfunction "PC5_P34") (pintype "bidirectional"))
    )
    (net (code "72") (name "/SHIFTREG_CLK") (class "Default")
      (node (ref "SV1") (pin "8") (pinfunction "8_8") (pintype "passive"))
      (node (ref "U$1") (pin "P85") (pinfunction "PD4_P85") (pintype "bidirectional"))
      (node (ref "U$8") (pin "T32") (pinfunction "T32_T32") (pintype "bidirectional"))
    )
    (net (code "73") (name "/SHIFTREG_DATA") (class "Default")
      (node (ref "SV1") (pin "9") (pinfunction "9_9") (pintype "passive"))
      (node (ref "U$1") (pin "P86") (pinfunction "PD5_P86") (pintype "bidirectional"))
      (node (ref "U$8") (pin "T33") (pinfunction "T33_T33") (pintype "bidirectional"))
    )
    (net (code "74") (name "/SHIFTREG_ENABLE") (class "Default")
      (node (ref "SV1") (pin "7") (pinfunction "7_7") (pintype "passive"))
      (node (ref "U$1") (pin "P84") (pinfunction "PD3_P84") (pintype "bidirectional"))
      (node (ref "U$8") (pin "T31") (pinfunction "T31_T31") (pintype "bidirectional"))
    )
    (net (code "75") (name "/SONAR_DAC") (class "Default")
      (node (ref "U$1") (pin "P29") (pinfunction "PA4_P29") (pintype "bidirectional"))
      (node (ref "U$8") (pin "B46") (pinfunction "B46_B46") (pintype "bidirectional"))
    )
    (net (code "76") (name "/SONAR_PWM") (class "Default")
      (node (ref "SV1") (pin "10") (pinfunction "10_10") (pintype "passive"))
      (node (ref "U$1") (pin "P89") (pinfunction "PB3_P89") (pintype "bidirectional"))
      (node (ref "U$8") (pin "T34") (pinfunction "T34_T34") (pintype "bidirectional"))
    )
    (net (code "77") (name "/TEMP_BACKUP") (class "Default")
      (node (ref "SV1") (pin "2") (pinfunction "2_2") (pintype "passive"))
      (node (ref "U$1") (pin "P79") (pinfunction "PC11_P79") (pintype "bidirectional"))
      (node (ref "U$8") (pin "T25") (pinfunction "T25_T25") (pintype "bidirectional"))
    )
    (net (code "78") (name "/USART3_RX") (class "Default")
      (node (ref "JP1") (pin "3") (pinfunction "3_3") (pintype "passive"))
      (node (ref "U$1") (pin "P48") (pinfunction "PB11_P48") (pintype "bidirectional"))
    )
    (net (code "79") (name "/USART3_TX") (class "Default")
      (node (ref "JP1") (pin "2") (pinfunction "2_2") (pintype "passive"))
      (node (ref "U$1") (pin "P47") (pinfunction "PB10_P47") (pintype "bidirectional"))
    )
    (net (code "80") (name "/USBPWR") (class "Default")
      (node (ref "SV2") (pin "13") (pinfunction "13_13") (pintype "passive"))
      (node (ref "T3") (pin "1") (pinfunction "D_1") (pintype "passive"))
      (node (ref "U$1") (pin "P68") (pinfunction "PA9_P68") (pintype "bidirectional"))
      (node (ref "U$5") (pin "P1") (pinfunction "VCC_P1") (pintype "bidirectional"))
    )
    (net (code "81") (name "/USB_D+") (class "Default")
      (node (ref "RN2") (pin "3") (pinfunction "2_3") (pintype "passive"))
      (node (ref "U$1") (pin "P71") (pinfunction "PA12_P71") (pintype "bidirectional"))
    )
    (net (code "82") (name "/USB_D-") (class "Default")
      (node (ref "RN2") (pin "4") (pinfunction "2_4") (pintype "passive"))
      (node (ref "U$1") (pin "P70") (pinfunction "PA11_P70") (pintype "bidirectional"))
    )
    (net (code "83") (name "/VDD_ETH") (class "Default")
      (node (ref "JP1") (pin "7") (pinfunction "7_7") (pintype "passive"))
    )
    (net (code "84") (name "GND") (class "Default")
      (node (ref "C1") (pin "2") (pinfunction "2_2") (pintype "passive"))
      (node (ref "C10") (pin "2") (pinfunction "2_2") (pintype "passive"))
      (node (ref "C11") (pin "2") (pinfunction "2_2") (pintype "passive"))
      (node (ref "C12") (pin "2") (pinfunction "2_2") (pintype "passive"))
      (node (ref "C13") (pin "2") (pinfunction "2_2") (pintype "passive"))
      (node (ref "C14") (pin "2") (pinfunction "2_2") (pintype "passive"))
      (node (ref "C17") (pin "2") (pinfunction "2_2") (pintype "passive"))
      (node (ref "C18") (pin "2") (pinfunction "2_2") (pintype "passive"))
      (node (ref "C2") (pin "2") (pinfunction "2_2") (pintype "passive"))
      (node (ref "C3") (pin "2") (pinfunction "2_2") (pintype "passive"))
      (node (ref "C4") (pin "2") (pinfunction "2_2") (pintype "passive"))
      (node (ref "C6") (pin "2") (pinfunction "2_2") (pintype "passive"))
      (node (ref "C8") (pin "2") (pinfunction "2_2") (pintype "passive"))
      (node (ref "C9") (pin "2") (pinfunction "2_2") (pintype "passive"))
      (node (ref "D2") (pin "C") (pinfunction "C_C") (pintype "passive"))
      (node (ref "D3") (pin "C") (pinfunction "C_C") (pintype "passive"))
      (node (ref "D4") (pin "C") (pinfunction "C_C") (pintype "passive"))
      (node (ref "D5") (pin "C") (pinfunction "C_C") (pintype "passive"))
      (node (ref "JP1") (pin "5") (pinfunction "5_5") (pintype "passive"))
      (node (ref "Q1") (pin "2") (pinfunction "GND_2") (pintype "power_in"))
      (node (ref "R1") (pin "1") (pinfunction "1_1") (pintype "passive"))
      (node (ref "R6") (pin "1") (pinfunction "1_1") (pintype "passive"))
      (node (ref "SV2") (pin "15") (pinfunction "15_15") (pintype "passive"))
      (node (ref "SV3") (pin "1") (pinfunction "1_1") (pintype "passive"))
      (node (ref "SV3") (pin "11") (pinfunction "11_11") (pintype "passive"))
      (node (ref "SV3") (pin "7") (pinfunction "7_7") (pintype "passive"))
      (node (ref "SV3") (pin "9") (pinfunction "9_9") (pintype "passive"))
      (node (ref "T4") (pin "GND") (pinfunction "GND_GND") (pintype "bidirectional"))
      (node (ref "U$1") (pin "P10") (pinfunction "VSS1_P10") (pintype "bidirectional"))
      (node (ref "U$1") (pin "P20") (pinfunction "VSSA_P20") (pintype "bidirectional"))
      (node (ref "U$1") (pin "P27") (pinfunction "VSS2_P27") (pintype "bidirectional"))
      (node (ref "U$1") (pin "P37") (pinfunction "PB2_P37") (pintype "bidirectional"))
      (node (ref "U$1") (pin "P74") (pinfunction "VSS3_P74") (pintype "bidirectional"))
      (node (ref "U$1") (pin "P99") (pinfunction "VSS4_P99") (pintype "bidirectional"))
      (node (ref "U$2") (pin "1") (pinfunction "P$1_1") (pintype "bidirectional"))
      (node (ref "U$5") (pin "GND1") (pinfunction "GND_GND1") (pintype "bidirectional"))
      (node (ref "U$5") (pin "GND2") (pinfunction "GND_GND2") (pintype "bidirectional"))
      (node (ref "U$5") (pin "GND3") (pinfunction "GND_GND3") (pintype "bidirectional"))
      (node (ref "U$5") (pin "GND4") (pinfunction "GND_GND4") (pintype "bidirectional"))
      (node (ref "U$5") (pin "GND7") (pinfunction "GND_GND7") (pintype "bidirectional"))
      (node (ref "U$5") (pin "GND8") (pinfunction "GND_GND8") (pintype "bidirectional"))
      (node (ref "U$5") (pin "P4") (pinfunction "ID_P4") (pintype "bidirectional"))
      (node (ref "U$5") (pin "P5") (pinfunction "GND_P5") (pintype "bidirectional"))
      (node (ref "U$6") (pin "2") (pinfunction "GND_2") (pintype "bidirectional"))
      (node (ref "U$8") (pin "T11") (pinfunction "T11_T11") (pintype "bidirectional"))
      (node (ref "U$8") (pin "T12") (pinfunction "T12_T12") (pintype "bidirectional"))
      (node (ref "U$8") (pin "T13") (pinfunction "T13_T13") (pintype "bidirectional"))
      (node (ref "U$8") (pin "T14") (pinfunction "T14_T14") (pintype "bidirectional"))
      (node (ref "U$8") (pin "T15") (pinfunction "T15_T15") (pintype "bidirectional"))
      (node (ref "U$8") (pin "T16") (pinfunction "T16_T16") (pintype "bidirectional"))
      (node (ref "U$8") (pin "T17") (pinfunction "T17_T17") (pintype "bidirectional"))
      (node (ref "U$8") (pin "T18") (pinfunction "T18_T18") (pintype "bidirectional"))
    )
    (net (code "85") (name "Net-(D2-PadA)") (class "Default")
      (node (ref "D2") (pin "A") (pinfunction "A_A") (pintype "passive"))
      (node (ref "R11") (pin "1") (pinfunction "1_1") (pintype "passive"))
    )
    (net (code "86") (name "Net-(D3-PadA)") (class "Default")
      (node (ref "D3") (pin "A") (pinfunction "A_A") (pintype "passive"))
      (node (ref "R12") (pin "1") (pinfunction "1_1") (pintype "passive"))
    )
    (net (code "87") (name "Net-(D4-PadA)") (class "Default")
      (node (ref "D4") (pin "A") (pinfunction "A_A") (pintype "passive"))
      (node (ref "R13") (pin "1") (pinfunction "1_1") (pintype "passive"))
    )
    (net (code "88") (name "Net-(D5-PadA)") (class "Default")
      (node (ref "D5") (pin "A") (pinfunction "A_A") (pintype "passive"))
      (node (ref "R14") (pin "1") (pinfunction "1_1") (pintype "passive"))
    )
    (net (code "89") (name "Net-(RN2B-1)") (class "Default")
      (node (ref "RN2") (pin "2") (pinfunction "1_2") (pintype "passive"))
      (node (ref "U$5") (pin "P3") (pinfunction "D+_P3") (pintype "bidirectional"))
    )
    (net (code "90") (name "Net-(T3-S)") (class "Default")
      (node (ref "C12") (pin "1") (pinfunction "1_1") (pintype "passive"))
      (node (ref "D6") (pin "C") (pinfunction "C_C") (pintype "passive"))
      (node (ref "T3") (pin "2") (pinfunction "S_2") (pintype "passive"))
      (node (ref "T4") (pin "VIN") (pinfunction "VIN_VIN") (pintype "input"))
    )
    (net (code "91") (name "Net-(U$1F-BOOT0)") (class "Default")
      (node (ref "R1") (pin "2") (pinfunction "2_2") (pintype "passive"))
      (node (ref "U$1") (pin "P94") (pinfunction "BOOT0_P94") (pintype "bidirectional"))
      (node (ref "U$3") (pin "2") (pinfunction "P$2_2") (pintype "bidirectional"))
    )
    (net (code "92") (name "Net-(U$1F-NRST)") (class "Default")
      (node (ref "R2") (pin "1") (pinfunction "1_1") (pintype "passive"))
      (node (ref "U$1") (pin "P14") (pinfunction "NRST_P14") (pintype "bidirectional"))
      (node (ref "U$2") (pin "2") (pinfunction "P$2_2") (pintype "bidirectional"))
    )
    (net (code "93") (name "Net-(U$1F-VCAP_1)") (class "Default")
      (node (ref "C3") (pin "1") (pinfunction "1_1") (pintype "passive"))
      (node (ref "U$1") (pin "P49") (pinfunction "VCAP_1_P49") (pintype "bidirectional"))
    )
    (net (code "94") (name "Net-(U$1F-VCAP_2)") (class "Default")
      (node (ref "C2") (pin "1") (pinfunction "1_1") (pintype "passive"))
      (node (ref "U$1") (pin "P73") (pinfunction "VCAP_2_P73") (pintype "bidirectional"))
    )
    (net (code "95") (name "Net-(U$5-D-)") (class "Default")
      (node (ref "RN2") (pin "1") (pinfunction "1_1") (pintype "passive"))
      (node (ref "U$5") (pin "P2") (pinfunction "D-_P2") (pintype "bidirectional"))
    )
    (net (code "96") (name "Net-(U$6-RS)") (class "Default")
      (node (ref "R6") (pin "2") (pinfunction "2_2") (pintype "passive"))
      (node (ref "U$6") (pin "8") (pinfunction "RS_8") (pintype "bidirectional"))
    )
    (net (code "97") (name "unconnected-(Q1-OE-Pad1)") (class "Default")
      (node (ref "Q1") (pin "1") (pinfunction "OE_1") (pintype "input"))
    )
    (net (code "98") (name "unconnected-(U$1A-PA1-PadP24)") (class "Default")
      (node (ref "U$1") (pin "P24") (pinfunction "PA1_P24") (pintype "bidirectional"))
    )
    (net (code "99") (name "unconnected-(U$1A-PA2-PadP25)") (class "Default")
      (node (ref "U$1") (pin "P25") (pinfunction "PA2_P25") (pintype "bidirectional"))
    )
    (net (code "100") (name "unconnected-(U$1B-PB12-PadP51)") (class "Default")
      (node (ref "U$1") (pin "P51") (pinfunction "PB12_P51") (pintype "bidirectional"))
    )
    (net (code "101") (name "unconnected-(U$1B-PB13-PadP52)") (class "Default")
      (node (ref "U$1") (pin "P52") (pinfunction "PB13_P52") (pintype "bidirectional"))
    )
    (net (code "102") (name "unconnected-(U$1C-PC1-PadP16)") (class "Default")
      (node (ref "U$1") (pin "P16") (pinfunction "PC1_P16") (pintype "bidirectional"))
    )
    (net (code "103") (name "unconnected-(U$6-SHDN-Pad5)") (class "Default")
      (node (ref "U$6") (pin "5") (pinfunction "SHDN_5") (pintype "bidirectional"))
    )
    (net (code "104") (name "unconnected-(U$8-PadB1)") (class "Default")
      (node (ref "U$8") (pin "B1") (pinfunction "B1_B1") (pintype "bidirectional"))
    )
    (net (code "105") (name "unconnected-(U$8-PadB2)") (class "Default")
      (node (ref "U$8") (pin "B2") (pinfunction "B2_B2") (pintype "bidirectional"))
    )
    (net (code "106") (name "unconnected-(U$8-PadB3)") (class "Default")
      (node (ref "U$8") (pin "B3") (pinfunction "B3_B3") (pintype "bidirectional"))
    )
    (net (code "107") (name "unconnected-(U$8-PadB4)") (class "Default")
      (node (ref "U$8") (pin "B4") (pinfunction "B4_B4") (pintype "bidirectional"))
    )
    (net (code "108") (name "unconnected-(U$8-PadB5)") (class "Default")
      (node (ref "U$8") (pin "B5") (pinfunction "B5_B5") (pintype "bidirectional"))
    )
    (net (code "109") (name "unconnected-(U$8-PadB6)") (class "Default")
      (node (ref "U$8") (pin "B6") (pinfunction "B6_B6") (pintype "bidirectional"))
    )
    (net (code "110") (name "unconnected-(U$8-PadB7)") (class "Default")
      (node (ref "U$8") (pin "B7") (pinfunction "B7_B7") (pintype "bidirectional"))
    )
    (net (code "111") (name "unconnected-(U$8-PadB8)") (class "Default")
      (node (ref "U$8") (pin "B8") (pinfunction "B8_B8") (pintype "bidirectional"))
    )
    (net (code "112") (name "unconnected-(U$8-PadB9)") (class "Default")
      (node (ref "U$8") (pin "B9") (pinfunction "B9_B9") (pintype "bidirectional"))
    )
    (net (code "113") (name "unconnected-(U$8-PadB10)") (class "Default")
      (node (ref "U$8") (pin "B10") (pinfunction "B10_B10") (pintype "bidirectional"))
    )
    (net (code "114") (name "unconnected-(U$8-PadB11)") (class "Default")
      (node (ref "U$8") (pin "B11") (pinfunction "B11_B11") (pintype "bidirectional"))
    )
    (net (code "115") (name "unconnected-(U$8-PadB12)") (class "Default")
      (node (ref "U$8") (pin "B12") (pinfunction "B12_B12") (pintype "bidirectional"))
    )
    (net (code "116") (name "unconnected-(U$8-PadB13)") (class "Default")
      (node (ref "U$8") (pin "B13") (pinfunction "B13_B13") (pintype "bidirectional"))
    )
    (net (code "117") (name "unconnected-(U$8-PadB14)") (class "Default")
      (node (ref "U$8") (pin "B14") (pinfunction "B14_B14") (pintype "bidirectional"))
    )
    (net (code "118") (name "unconnected-(U$8-PadB15)") (class "Default")
      (node (ref "U$8") (pin "B15") (pinfunction "B15_B15") (pintype "bidirectional"))
    )
    (net (code "119") (name "unconnected-(U$8-PadB16)") (class "Default")
      (node (ref "U$8") (pin "B16") (pinfunction "B16_B16") (pintype "bidirectional"))
    )
    (net (code "120") (name "unconnected-(U$8-PadB17)") (class "Default")
      (node (ref "U$8") (pin "B17") (pinfunction "B17_B17") (pintype "bidirectional"))
    )
    (net (code "121") (name "unconnected-(U$8-PadB18)") (class "Default")
      (node (ref "U$8") (pin "B18") (pinfunction "B18_B18") (pintype "bidirectional"))
    )
    (net (code "122") (name "unconnected-(U$8-PadB19)") (class "Default")
      (node (ref "U$8") (pin "B19") (pinfunction "B19_B19") (pintype "bidirectional"))
    )
    (net (code "123") (name "unconnected-(U$8-PadB20)") (class "Default")
      (node (ref "U$8") (pin "B20") (pinfunction "B20_B20") (pintype "bidirectional"))
    )
    (net (code "124") (name "unconnected-(U$8-PadB21)") (class "Default")
      (node (ref "U$8") (pin "B21") (pinfunction "B21_B21") (pintype "bidirectional"))
    )
    (net (code "125") (name "unconnected-(U$8-PadB22)") (class "Default")
      (node (ref "U$8") (pin "B22") (pinfunction "B22_B22") (pintype "bidirectional"))
    )
    (net (code "126") (name "unconnected-(U$8-PadB23)") (class "Default")
      (node (ref "U$8") (pin "B23") (pinfunction "B23_B23") (pintype "bidirectional"))
    )
    (net (code "127") (name "unconnected-(U$8-PadB24)") (class "Default")
      (node (ref "U$8") (pin "B24") (pinfunction "B24_B24") (pintype "bidirectional"))
    )
    (net (code "128") (name "unconnected-(U$8-PadB25)") (class "Default")
      (node (ref "U$8") (pin "B25") (pinfunction "B25_B25") (pintype "bidirectional"))
    )
    (net (code "129") (name "unconnected-(U$8-PadB26)") (class "Default")
      (node (ref "U$8") (pin "B26") (pinfunction "B26_B26") (pintype "bidirectional"))
    )
    (net (code "130") (name "unconnected-(U$8-PadB27)") (class "Default")
      (node (ref "U$8") (pin "B27") (pinfunction "B27_B27") (pintype "bidirectional"))
    )
    (net (code "131") (name "unconnected-(U$8-PadB28)") (class "Default")
      (node (ref "U$8") (pin "B28") (pinfunction "B28_B28") (pintype "bidirectional"))
    )
    (net (code "132") (name "unconnected-(U$8-PadB29)") (class "Default")
      (node (ref "U$8") (pin "B29") (pinfunction "B29_B29") (pintype "bidirectional"))
    )
    (net (code "133") (name "unconnected-(U$8-PadB30)") (class "Default")
      (node (ref "U$8") (pin "B30") (pinfunction "B30_B30") (pintype "bidirectional"))
    )
    (net (code "134") (name "unconnected-(U$8-PadB31)") (class "Default")
      (node (ref "U$8") (pin "B31") (pinfunction "B31_B31") (pintype "bidirectional"))
    )
    (net (code "135") (name "unconnected-(U$8-PadB32)") (class "Default")
      (node (ref "U$8") (pin "B32") (pinfunction "B32_B32") (pintype "bidirectional"))
    )
    (net (code "136") (name "unconnected-(U$8-PadB33)") (class "Default")
      (node (ref "U$8") (pin "B33") (pinfunction "B33_B33") (pintype "bidirectional"))
    )
    (net (code "137") (name "unconnected-(U$8-PadB34)") (class "Default")
      (node (ref "U$8") (pin "B34") (pinfunction "B34_B34") (pintype "bidirectional"))
    )
    (net (code "138") (name "unconnected-(U$8-PadB37)") (class "Default")
      (node (ref "U$8") (pin "B37") (pinfunction "B37_B37") (pintype "bidirectional"))
    )
    (net (code "139") (name "unconnected-(U$8-PadB38)") (class "Default")
      (node (ref "U$8") (pin "B38") (pinfunction "B38_B38") (pintype "bidirectional"))
    )
    (net (code "140") (name "unconnected-(U$8-PadB39)") (class "Default")
      (node (ref "U$8") (pin "B39") (pinfunction "B39_B39") (pintype "bidirectional"))
    )
    (net (code "141") (name "unconnected-(U$8-PadB40)") (class "Default")
      (node (ref "U$8") (pin "B40") (pinfunction "B40_B40") (pintype "bidirectional"))
    )
    (net (code "142") (name "unconnected-(U$8-PadB41)") (class "Default")
      (node (ref "U$8") (pin "B41") (pinfunction "B41_B41") (pintype "bidirectional"))
    )
    (net (code "143") (name "unconnected-(U$8-PadB42)") (class "Default")
      (node (ref "U$8") (pin "B42") (pinfunction "B42_B42") (pintype "bidirectional"))
    )
    (net (code "144") (name "unconnected-(U$8-PadB43)") (class "Default")
      (node (ref "U$8") (pin "B43") (pinfunction "B43_B43") (pintype "bidirectional"))
    )
    (net (code "145") (name "unconnected-(U$8-PadB44)") (class "Default")
      (node (ref "U$8") (pin "B44") (pinfunction "B44_B44") (pintype "bidirectional"))
    )
    (net (code "146") (name "unconnected-(U$8-PadB45)") (class "Default")
      (node (ref "U$8") (pin "B45") (pinfunction "B45_B45") (pintype "bidirectional"))
    )
    (net (code "147") (name "unconnected-(U$8-PadB47)") (class "Default")
      (node (ref "U$8") (pin "B47") (pinfunction "B47_B47") (pintype "bidirectional"))
    )
    (net (code "148") (name "unconnected-(U$8-PadB48)") (class "Default")
      (node (ref "U$8") (pin "B48") (pinfunction "B48_B48") (pintype "bidirectional"))
    )
    (net (code "149") (name "unconnected-(U$8-PadB49)") (class "Default")
      (node (ref "U$8") (pin "B49") (pinfunction "B49_B49") (pintype "bidirectional"))
    )
    (net (code "150") (name "unconnected-(U$8-PadB50)") (class "Default")
      (node (ref "U$8") (pin "B50") (pinfunction "B50_B50") (pintype "bidirectional"))
    )
    (net (code "151") (name "unconnected-(U$8-PadB51)") (class "Default")
      (node (ref "U$8") (pin "B51") (pinfunction "B51_B51") (pintype "bidirectional"))
    )
    (net (code "152") (name "unconnected-(U$8-PadB52)") (class "Default")
      (node (ref "U$8") (pin "B52") (pinfunction "B52_B52") (pintype "bidirectional"))
    )
    (net (code "153") (name "unconnected-(U$8-PadB53)") (class "Default")
      (node (ref "U$8") (pin "B53") (pinfunction "B53_B53") (pintype "bidirectional"))
    )
    (net (code "154") (name "unconnected-(U$8-PadB54)") (class "Default")
      (node (ref "U$8") (pin "B54") (pinfunction "B54_B54") (pintype "bidirectional"))
    )
    (net (code "155") (name "unconnected-(U$8-PadB55)") (class "Default")
      (node (ref "U$8") (pin "B55") (pinfunction "B55_B55") (pintype "bidirectional"))
    )
    (net (code "156") (name "unconnected-(U$8-PadB56)") (class "Default")
      (node (ref "U$8") (pin "B56") (pinfunction "B56_B56") (pintype "bidirectional"))
    )
    (net (code "157") (name "unconnected-(U$8-PadB57)") (class "Default")
      (node (ref "U$8") (pin "B57") (pinfunction "B57_B57") (pintype "bidirectional"))
    )
    (net (code "158") (name "unconnected-(U$8-PadB58)") (class "Default")
      (node (ref "U$8") (pin "B58") (pinfunction "B58_B58") (pintype "bidirectional"))
    )
    (net (code "159") (name "unconnected-(U$8-PadB59)") (class "Default")
      (node (ref "U$8") (pin "B59") (pinfunction "B59_B59") (pintype "bidirectional"))
    )
    (net (code "160") (name "unconnected-(U$8-PadB60)") (class "Default")
      (node (ref "U$8") (pin "B60") (pinfunction "B60_B60") (pintype "bidirectional"))
    )
    (net (code "161") (name "unconnected-(U$8-PadT7)") (class "Default")
      (node (ref "U$8") (pin "T7") (pinfunction "T7_T7") (pintype "bidirectional"))
    )
    (net (code "162") (name "unconnected-(U$8-PadT8)") (class "Default")
      (node (ref "U$8") (pin "T8") (pinfunction "T8_T8") (pintype "bidirectional"))
    )
    (net (code "163") (name "unconnected-(U$8-PadT9)") (class "Default")
      (node (ref "U$8") (pin "T9") (pinfunction "T9_T9") (pintype "bidirectional"))
    )
    (net (code "164") (name "unconnected-(U$8-PadT10)") (class "Default")
      (node (ref "U$8") (pin "T10") (pinfunction "T10_T10") (pintype "bidirectional"))
    )
    (net (code "165") (name "unconnected-(U$8-PadT19)") (class "Default")
      (node (ref "U$8") (pin "T19") (pinfunction "T19_T19") (pintype "bidirectional"))
    )
    (net (code "166") (name "unconnected-(U$8-PadT20)") (class "Default")
      (node (ref "U$8") (pin "T20") (pinfunction "T20_T20") (pintype "bidirectional"))
    )
    (net (code "167") (name "unconnected-(U$8-PadT21)") (class "Default")
      (node (ref "U$8") (pin "T21") (pinfunction "T21_T21") (pintype "bidirectional"))
    )
    (net (code "168") (name "unconnected-(U$8-PadT22)") (class "Default")
      (node (ref "U$8") (pin "T22") (pinfunction "T22_T22") (pintype "bidirectional"))
    )
    (net (code "169") (name "unconnected-(U$8-PadT23)") (class "Default")
      (node (ref "U$8") (pin "T23") (pinfunction "T23_T23") (pintype "bidirectional"))
    )
    (net (code "170") (name "unconnected-(U$8-PadT24)") (class "Default")
      (node (ref "U$8") (pin "T24") (pinfunction "T24_T24") (pintype "bidirectional"))
    )
    (net (code "171") (name "unconnected-(U$8-PadT26)") (class "Default")
      (node (ref "U$8") (pin "T26") (pinfunction "T26_T26") (pintype "bidirectional"))
    )
    (net (code "172") (name "unconnected-(U$8-PadT27)") (class "Default")
      (node (ref "U$8") (pin "T27") (pinfunction "T27_T27") (pintype "bidirectional"))
    )
    (net (code "173") (name "unconnected-(U$8-PadT28)") (class "Default")
      (node (ref "U$8") (pin "T28") (pinfunction "T28_T28") (pintype "bidirectional"))
    )
    (net (code "174") (name "unconnected-(U$8-PadT29)") (class "Default")
      (node (ref "U$8") (pin "T29") (pinfunction "T29_T29") (pintype "bidirectional"))
    )
    (net (code "175") (name "unconnected-(U$8-PadT30)") (class "Default")
      (node (ref "U$8") (pin "T30") (pinfunction "T30_T30") (pintype "bidirectional"))
    )
    (net (code "176") (name "unconnected-(U$8-PadT35)") (class "Default")
      (node (ref "U$8") (pin "T35") (pinfunction "T35_T35") (pintype "bidirectional"))
    )
    (net (code "177") (name "unconnected-(U$8-PadT36)") (class "Default")
      (node (ref "U$8") (pin "T36") (pinfunction "T36_T36") (pintype "bidirectional"))
    )
    (net (code "178") (name "unconnected-(U$8-PadT40)") (class "Default")
      (node (ref "U$8") (pin "T40") (pinfunction "T40_T40") (pintype "bidirectional"))
    )
    (net (code "179") (name "unconnected-(U$8-PadT43)") (class "Default")
      (node (ref "U$8") (pin "T43") (pinfunction "T43_T43") (pintype "bidirectional"))
    )
    (net (code "180") (name "unconnected-(U$8-PadT44)") (class "Default")
      (node (ref "U$8") (pin "T44") (pinfunction "T44_T44") (pintype "bidirectional"))
    )
    (net (code "181") (name "unconnected-(U$8-PadT45)") (class "Default")
      (node (ref "U$8") (pin "T45") (pinfunction "T45_T45") (pintype "bidirectional"))
    )
    (net (code "182") (name "unconnected-(U$8-PadT46)") (class "Default")
      (node (ref "U$8") (pin "T46") (pinfunction "T46_T46") (pintype "bidirectional"))
    )
    (net (code "183") (name "unconnected-(U$8-PadT47)") (class "Default")
      (node (ref "U$8") (pin "T47") (pinfunction "T47_T47") (pintype "bidirectional"))
    )
    (net (code "184") (name "unconnected-(U$8-PadT48)") (class "Default")
      (node (ref "U$8") (pin "T48") (pinfunction "T48_T48") (pintype "bidirectional"))
    )
    (net (code "185") (name "unconnected-(U$8-PadT49)") (class "Default")
      (node (ref "U$8") (pin "T49") (pinfunction "T49_T49") (pintype "bidirectional"))
    )
    (net (code "186") (name "unconnected-(U$8-PadT50)") (class "Default")
      (node (ref "U$8") (pin "T50") (pinfunction "T50_T50") (pintype "bidirectional"))
    )
    (net (code "187") (name "unconnected-(U$8-PadT51)") (class "Default")
      (node (ref "U$8") (pin "T51") (pinfunction "T51_T51") (pintype "bidirectional"))
    )
    (net (code "188") (name "unconnected-(U$8-PadT52)") (class "Default")
      (node (ref "U$8") (pin "T52") (pinfunction "T52_T52") (pintype "bidirectional"))
    )
    (net (code "189") (name "unconnected-(U$8-PadT53)") (class "Default")
      (node (ref "U$8") (pin "T53") (pinfunction "T53_T53") (pintype "bidirectional"))
    )
    (net (code "190") (name "unconnected-(U$8-PadT54)") (class "Default")
      (node (ref "U$8") (pin "T54") (pinfunction "T54_T54") (pintype "bidirectional"))
    )
    (net (code "191") (name "unconnected-(U$8-PadT55)") (class "Default")
      (node (ref "U$8") (pin "T55") (pinfunction "T55_T55") (pintype "bidirectional"))
    )
    (net (code "192") (name "unconnected-(U$8-PadT56)") (class "Default")
      (node (ref "U$8") (pin "T56") (pinfunction "T56_T56") (pintype "bidirectional"))
    )
    (net (code "193") (name "unconnected-(U$8-PadT57)") (class "Default")
      (node (ref "U$8") (pin "T57") (pinfunction "T57_T57") (pintype "bidirectional"))
    )
    (net (code "194") (name "unconnected-(U$8-PadT58)") (class "Default")
      (node (ref "U$8") (pin "T58") (pinfunction "T58_T58") (pintype "bidirectional"))
    )
    (net (code "195") (name "unconnected-(U$8-PadT59)") (class "Default")
      (node (ref "U$8") (pin "T59") (pinfunction "T59_T59") (pintype "bidirectional"))
    )
  )
)
